# Sensors.net
KiCad netlist of a schematic drawn in Altium Designer
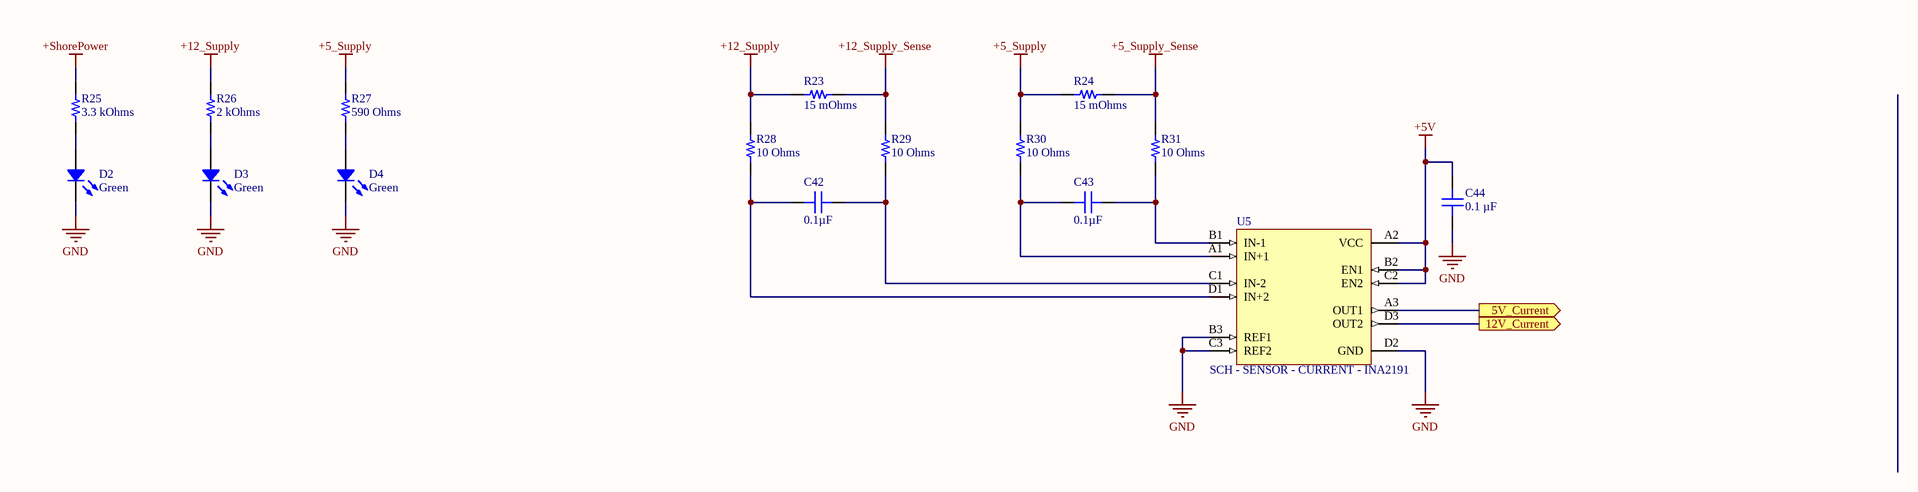
[diagram p0: Sensors.SchDoc]

(export (version "E")
  (design (tool "Eeschema 10.0.6"))
  (components
    (comp (ref "C42")
      (value "0.1µF")
      (footprint "CAP 0603_1608")
      (description "CAP CER 0.1UF 25V X7R 0603")
      (fields
        (field (name "PART NUMBER") "CL10B104KA8WPNC")
        (field (name "MANUFACTURER") "Samsung Electro-Mechanics")
      )
      (libsource (lib "Celestial Altium Library - altium_library") (part "Capacitor"))
    )
    (comp (ref "C43")
      (value "0.1µF")
      (footprint "CAP 0603_1608")
      (description "CAP CER 0.1UF 25V X7R 0603")
      (fields
        (field (name "PART NUMBER") "CL10B104KA8WPNC")
        (field (name "MANUFACTURER") "Samsung Electro-Mechanics")
      )
      (libsource (lib "Celestial Altium Library - altium_library") (part "Capacitor"))
    )
    (comp (ref "C44")
      (value "0.1 µF")
      (footprint "CAP 0603_1608")
      (description "CAP CER 0.1UF 50V X7R 0603")
      (fields
        (field (name "PART NUMBER") "CL10B104KB8NNWC")
        (field (name "MANUFACTURER") "Samsung Electro-Mechanics")
      )
      (libsource (lib "Celestial Altium Library - altium_library") (part "Capacitor"))
    )
    (comp (ref "D2")
      (value "Green")
      (footprint "LED 0603_1608 GREEN")
      (description "LED GREEN CLEAR CHIP SMD")
      (fields (field (name "PART NUMBER") "LTST-C193KGKT-5A") (field (name "MANUFACTURER") "Lite-On Inc."))
      (libsource (lib "Celestial Altium Library - altium_library") (part "LED"))
    )
    (comp (ref "D3")
      (value "Green")
      (footprint "LED 0603_1608 GREEN")
      (description "LED GREEN CLEAR CHIP SMD")
      (fields (field (name "PART NUMBER") "LTST-C193KGKT-5A") (field (name "MANUFACTURER") "Lite-On Inc."))
      (libsource (lib "Celestial Altium Library - altium_library") (part "LED"))
    )
    (comp (ref "D4")
      (value "Green")
      (footprint "LED 0603_1608 GREEN")
      (description "LED GREEN CLEAR CHIP SMD")
      (fields (field (name "PART NUMBER") "LTST-C193KGKT-5A") (field (name "MANUFACTURER") "Lite-On Inc."))
      (libsource (lib "Celestial Altium Library - altium_library") (part "LED"))
    )
    (comp (ref "R23")
      (value "15 mOhms")
      (footprint "RES 1206_3216")
      (description "RES 0.015 OHM 1% 1/2W 1206")
      (fields (field (name "PART NUMBER") "L4T12FR015FER") (field (name "MANUFACTURER") "Ohmite"))
      (libsource (lib "Celestial Altium Library - altium_library") (part "Resistor"))
    )
    (comp (ref "R24")
      (value "15 mOhms")
      (footprint "RES 1206_3216")
      (description "RES 0.015 OHM 1% 1/2W 1206")
      (fields (field (name "PART NUMBER") "L4T12FR015FER") (field (name "MANUFACTURER") "Ohmite"))
      (libsource (lib "Celestial Altium Library - altium_library") (part "Resistor"))
    )
    (comp (ref "R25")
      (value "3.3 kOhms")
      (footprint "RES 0603_1608")
      (description "RES 3.3K OHM 1% 1/10W 0603")
      (fields
        (field (name "PART NUMBER") "RMCF0603FT3K30")
        (field (name "MANUFACTURER") "Stackpole Electronics Inc")
      )
      (libsource (lib "Celestial Altium Library - altium_library") (part "Resistor"))
    )
    (comp (ref "R26")
      (value "2 kOhms")
      (footprint "RES 0603_1608")
      (description "RES 2K OHM 1% 1/8W 0603")
      (fields
        (field (name "PART NUMBER") "RNCP0603FTD2K00")
        (field (name "MANUFACTURER") "Stackpole Electronics Inc")
      )
      (libsource (lib "Celestial Altium Library - altium_library") (part "Resistor"))
    )
    (comp (ref "R27")
      (value "590 Ohms")
      (footprint "RES 0603_1608")
      (description "RES 590 OHM 1% 1/10W 0603")
      (fields
        (field (name "PART NUMBER") "RMCF0603FT590R")
        (field (name "MANUFACTURER") "Stackpole Electronics Inc")
      )
      (libsource (lib "Celestial Altium Library - altium_library") (part "Resistor"))
    )
    (comp (ref "R28")
      (value "10 Ohms")
      (footprint "RES 0603_1608")
      (description "CRGCQ 0603 10R 1%")
      (fields
        (field (name "PART NUMBER") "CRGCQ0603F10R")
        (field (name "MANUFACTURER") "TE Connectivity Passive Product")
      )
      (libsource (lib "Celestial Altium Library - altium_library") (part "Resistor"))
    )
    (comp (ref "R29")
      (value "10 Ohms")
      (footprint "RES 0603_1608")
      (description "CRGCQ 0603 10R 1%")
      (fields
        (field (name "PART NUMBER") "CRGCQ0603F10R")
        (field (name "MANUFACTURER") "TE Connectivity Passive Product")
      )
      (libsource (lib "Celestial Altium Library - altium_library") (part "Resistor"))
    )
    (comp (ref "R30")
      (value "10 Ohms")
      (footprint "RES 0603_1608")
      (description "CRGCQ 0603 10R 1%")
      (fields
        (field (name "PART NUMBER") "CRGCQ0603F10R")
        (field (name "MANUFACTURER") "TE Connectivity Passive Product")
      )
      (libsource (lib "Celestial Altium Library - altium_library") (part "Resistor"))
    )
    (comp (ref "R31")
      (value "10 Ohms")
      (footprint "RES 0603_1608")
      (description "CRGCQ 0603 10R 1%")
      (fields
        (field (name "PART NUMBER") "CRGCQ0603F10R")
        (field (name "MANUFACTURER") "TE Connectivity Passive Product")
      )
      (libsource (lib "Celestial Altium Library - altium_library") (part "Resistor"))
    )
    (comp (ref "U5")
      (value "SCH - SENSOR - CURRENT - INA2191")
      (footprint "PCB - LEADLESS - BGA - TI DSBGA-12")
      (libsource (lib "HAB_ICs") (part "SCH - SENSOR - CURRENT - INA2191"))
    )
  )
  (nets
    (net (code "1") (name "+5V") (class "Default")
      (node (ref "C44") (pin "1") (pinfunction "1_1") (pintype "passive"))
      (node (ref "U5") (pin "A2") (pinfunction "VCC_A2") (pintype "power_in"))
      (node (ref "U5") (pin "B2") (pinfunction "EN1_B2") (pintype "input"))
      (node (ref "U5") (pin "C2") (pinfunction "EN2_C2") (pintype "input"))
    )
    (net (code "2") (name "+5_Supply") (class "Default")
      (node (ref "R24") (pin "1") (pinfunction "1_1") (pintype "passive"))
      (node (ref "R27") (pin "2") (pinfunction "2_2") (pintype "passive"))
      (node (ref "R30") (pin "2") (pinfunction "2_2") (pintype "passive"))
    )
    (net (code "3") (name "+5_Supply_Sense") (class "Default")
      (node (ref "R24") (pin "2") (pinfunction "2_2") (pintype "passive"))
      (node (ref "R31") (pin "2") (pinfunction "2_2") (pintype "passive"))
    )
    (net (code "4") (name "+12_Supply") (class "Default")
      (node (ref "R23") (pin "1") (pinfunction "1_1") (pintype "passive"))
      (node (ref "R26") (pin "2") (pinfunction "2_2") (pintype "passive"))
      (node (ref "R28") (pin "2") (pinfunction "2_2") (pintype "passive"))
    )
    (net (code "5") (name "+12_Supply_Sense") (class "Default")
      (node (ref "R23") (pin "2") (pinfunction "2_2") (pintype "passive"))
      (node (ref "R29") (pin "2") (pinfunction "2_2") (pintype "passive"))
    )
    (net (code "6") (name "+ShorePower") (class "Default")
      (node (ref "R25") (pin "2") (pinfunction "2_2") (pintype "passive"))
    )
    (net (code "7") (name "/5V_Current") (class "Default")
      (node (ref "U5") (pin "A3") (pinfunction "OUT1_A3") (pintype "output"))
    )
    (net (code "8") (name "/12V_Current") (class "Default")
      (node (ref "U5") (pin "D3") (pinfunction "OUT2_D3") (pintype "output"))
    )
    (net (code "9") (name "GND") (class "Default")
      (node (ref "C44") (pin "2") (pinfunction "2_2") (pintype "passive"))
      (node (ref "D2") (pin "2") (pinfunction "2_2") (pintype "passive"))
      (node (ref "D3") (pin "2") (pinfunction "2_2") (pintype "passive"))
      (node (ref "D4") (pin "2") (pinfunction "2_2") (pintype "passive"))
      (node (ref "U5") (pin "B3") (pinfunction "REF1_B3") (pintype "input"))
      (node (ref "U5") (pin "C3") (pinfunction "REF2_C3") (pintype "input"))
      (node (ref "U5") (pin "D2") (pinfunction "GND_D2") (pintype "power_in"))
    )
    (net (code "10") (name "Net-(D2-Pad1)") (class "Default")
      (node (ref "D2") (pin "1") (pinfunction "1_1") (pintype "passive"))
      (node (ref "R25") (pin "1") (pinfunction "1_1") (pintype "passive"))
    )
    (net (code "11") (name "Net-(D3-Pad1)") (class "Default")
      (node (ref "D3") (pin "1") (pinfunction "1_1") (pintype "passive"))
      (node (ref "R26") (pin "1") (pinfunction "1_1") (pintype "passive"))
    )
    (net (code "12") (name "Net-(D4-Pad1)") (class "Default")
      (node (ref "D4") (pin "1") (pinfunction "1_1") (pintype "passive"))
      (node (ref "R27") (pin "1") (pinfunction "1_1") (pintype "passive"))
    )
    (net (code "13") (name "Net-(U5-IN+1)") (class "Default")
      (node (ref "C43") (pin "2") (pinfunction "2_2") (pintype "passive"))
      (node (ref "R30") (pin "1") (pinfunction "1_1") (pintype "passive"))
      (node (ref "U5") (pin "A1") (pinfunction "IN+1_A1") (pintype "input"))
    )
    (net (code "14") (name "Net-(U5-IN+2)") (class "Default")
      (node (ref "C42") (pin "2") (pinfunction "2_2") (pintype "passive"))
      (node (ref "R28") (pin "1") (pinfunction "1_1") (pintype "passive"))
      (node (ref "U5") (pin "D1") (pinfunction "IN+2_D1") (pintype "input"))
    )
    (net (code "15") (name "Net-(U5-IN-1)") (class "Default")
      (node (ref "C43") (pin "1") (pinfunction "1_1") (pintype "passive"))
      (node (ref "R31") (pin "1") (pinfunction "1_1") (pintype "passive"))
      (node (ref "U5") (pin "B1") (pinfunction "IN-1_B1") (pintype "input"))
    )
    (net (code "16") (name "Net-(U5-IN-2)") (class "Default")
      (node (ref "C42") (pin "1") (pinfunction "1_1") (pintype "passive"))
      (node (ref "R29") (pin "1") (pinfunction "1_1") (pintype "passive"))
      (node (ref "U5") (pin "C1") (pinfunction "IN-2_C1") (pintype "input"))
    )
  )
)
